# Display.net
KiCad netlist of a schematic drawn in EAGLE
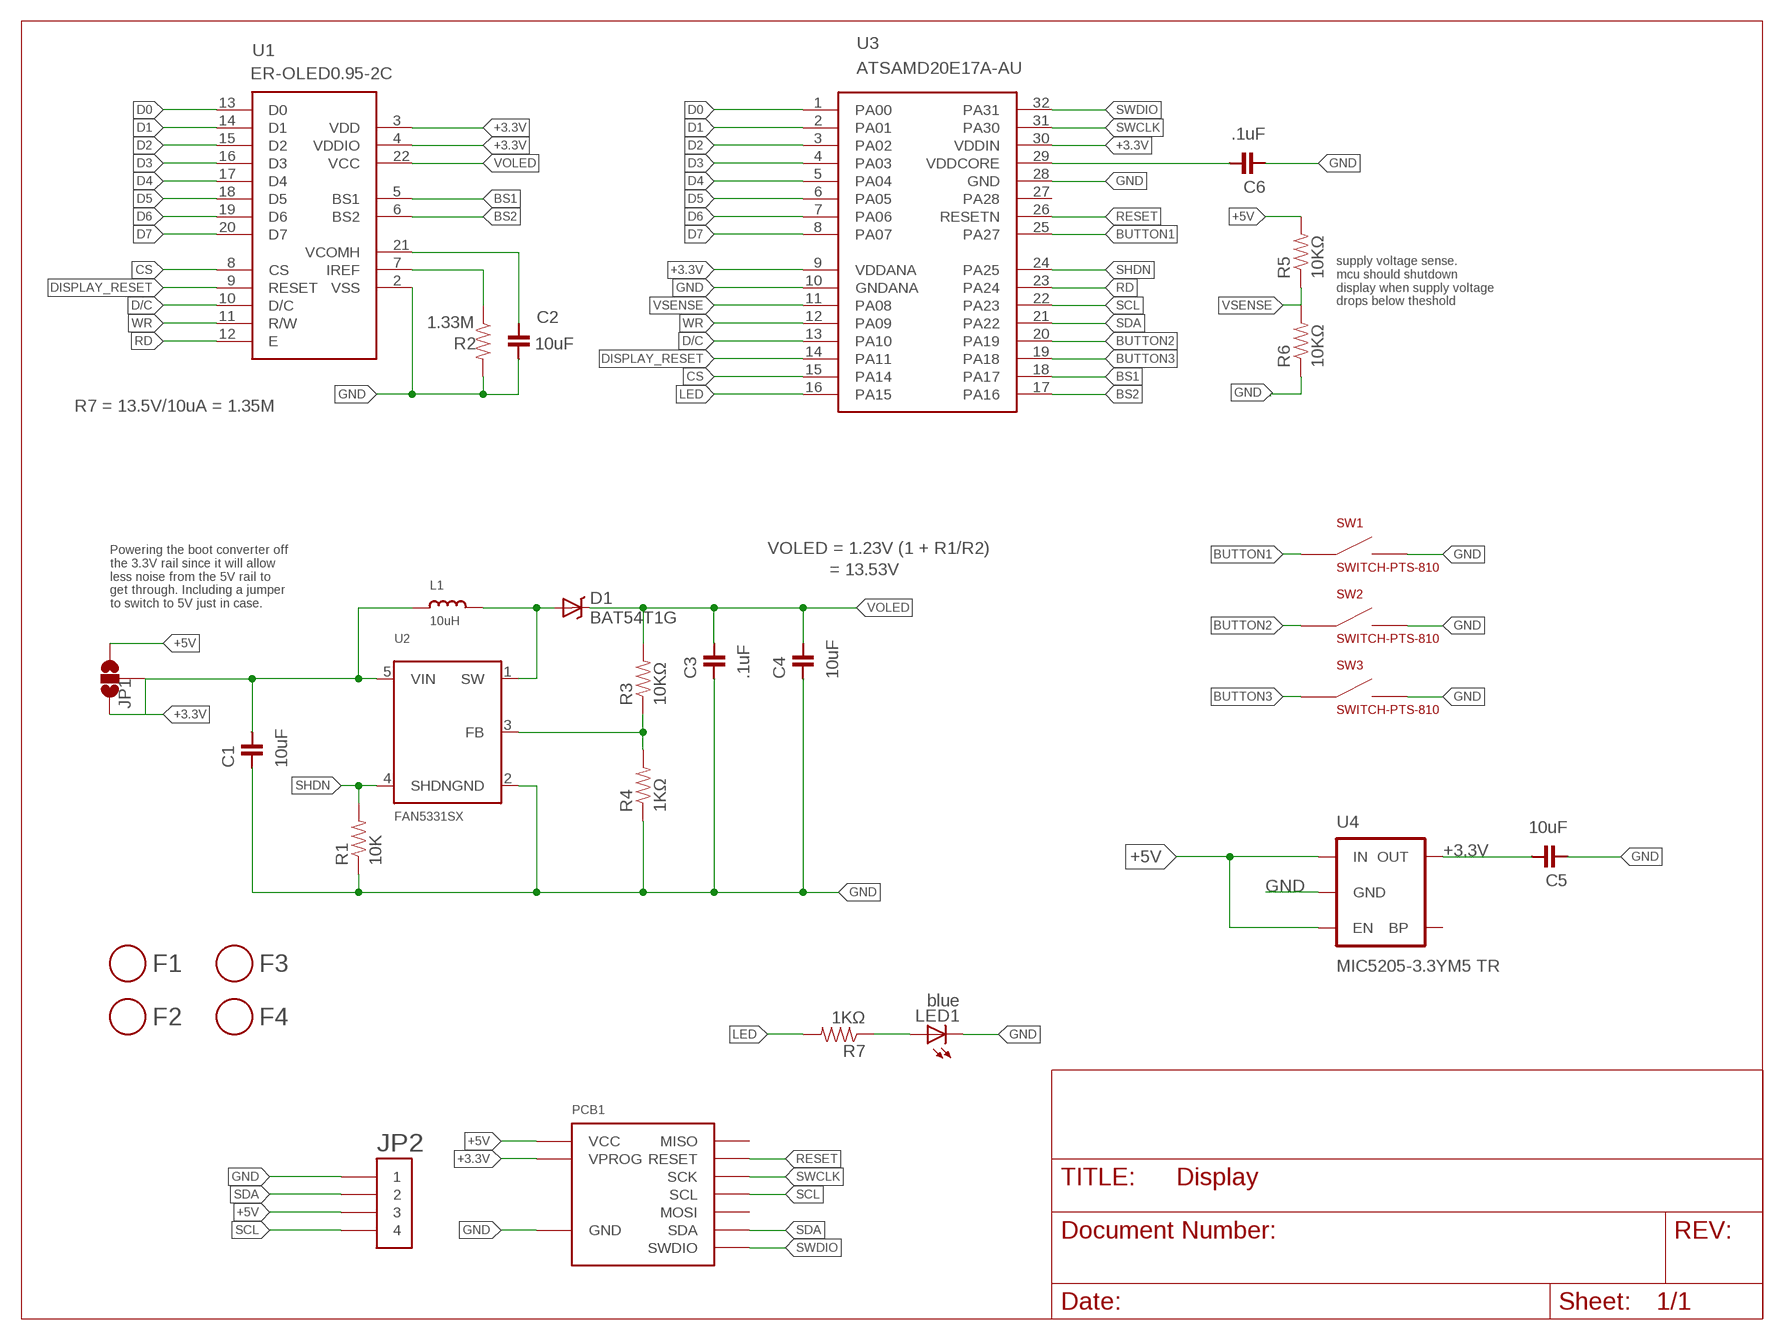
[diagram p0: schematic, sheet 1]

(export (version "E")
  (design (tool "Eeschema 10.0.6"))
  (components
    (comp (ref "C1")
      (value "10uF")
      (footprint "eagle-import:0603")
      (fields (field (name "PARTNUM") "GRM188R61C106MA73D"))
      (libsource (lib "eagle-import") (part "CAPACITOR-10UF"))
    )
    (comp (ref "C2")
      (value "10uF")
      (footprint "eagle-import:0603")
      (fields (field (name "PARTNUM") "GRM188R61C106MA73D"))
      (libsource (lib "eagle-import") (part "CAPACITOR-10UF"))
    )
    (comp (ref "C3")
      (value ".1uF")
      (footprint "eagle-import:0603")
      (fields (field (name "PARTNUM") "C0603C104K5RACTU"))
      (libsource (lib "eagle-import") (part "CAPACITOR-.1UF"))
    )
    (comp (ref "C4")
      (value "10uF")
      (footprint "eagle-import:0603")
      (fields (field (name "PARTNUM") "GRM188R61C106MA73D"))
      (libsource (lib "eagle-import") (part "CAPACITOR-10UF"))
    )
    (comp (ref "C5")
      (value "10uF")
      (footprint "eagle-import:0603")
      (fields (field (name "PARTNUM") "GRM188R61C106MA73D"))
      (libsource (lib "eagle-import") (part "CAPACITOR-10UF"))
    )
    (comp (ref "C6")
      (value ".1uF")
      (footprint "eagle-import:0603")
      (fields (field (name "PARTNUM") "C0603C104K5RACTU"))
      (libsource (lib "eagle-import") (part "CAPACITOR-.1UF"))
    )
    (comp (ref "D1")
      (value "BAT54T1G")
      (footprint "eagle-import:SMP")
      (fields (field (name "PARTNUM") "SS3P3-M3/84A"))
      (libsource (lib "eagle-import") (part "DIODE-SCHOTTKY"))
    )
    (comp (ref "F1")
      (value "FIDUCIAL")
      (footprint "eagle-import:FIDUCIAL_1MM")
      (libsource (lib "eagle-import") (part "FIDUCIAL"))
    )
    (comp (ref "F2")
      (value "FIDUCIAL")
      (footprint "eagle-import:FIDUCIAL_1MM")
      (libsource (lib "eagle-import") (part "FIDUCIAL"))
    )
    (comp (ref "F3")
      (value "FIDUCIAL")
      (footprint "eagle-import:FIDUCIAL_1MM")
      (libsource (lib "eagle-import") (part "FIDUCIAL"))
    )
    (comp (ref "F4")
      (value "FIDUCIAL")
      (footprint "eagle-import:FIDUCIAL_1MM")
      (libsource (lib "eagle-import") (part "FIDUCIAL"))
    )
    (comp (ref "JP1")
      (value "SOLDERJUMPER_2WAYS")
      (footprint "eagle-import:SJ_3")
      (libsource (lib "eagle-import") (part "SOLDERJUMPER_2WAYS"))
    )
    (comp (ref "JP2")
      (value "HEADER-1X4-AMPMODU")
      (footprint "eagle-import:AMPMODU-4P")
      (fields (field (name "PARTNUM") "147721-3"))
      (libsource (lib "eagle-import") (part "HEADER-1X4-AMPMODU"))
    )
    (comp (ref "L1")
      (value "10uH")
      (footprint "eagle-import:INDUCTOR_1007")
      (fields (field (name "PARTNUM") "MPI2520R1-100-R"))
      (libsource (lib "eagle-import") (part "INDUCTOR"))
    )
    (comp (ref "LED1")
      (value "blue")
      (footprint "eagle-import:0805-LED")
      (fields (field (name "PARTNUM") "LTST-C171TBKT"))
      (libsource (lib "eagle-import") (part "LED-0805-BLUE"))
    )
    (comp (ref "PCB1")
      (value "DEVICE-PCB")
      (footprint "eagle-import:DEVICE-PCB")
      (fields
        (field (name "BOARD") "Display")
        (field (name "PARTNUM") "Display PCB")
        (field (name "VERSION") "4")
      )
      (libsource (lib "eagle-import") (part "DEVICE-PCB"))
    )
    (comp (ref "R1")
      (value "10K")
      (footprint "eagle-import:0603")
      (fields (field (name "PARTNUM") "ERJ-3EKF1002V"))
      (libsource (lib "eagle-import") (part "RESISTOR-10KΩ"))
    )
    (comp (ref "R2")
      (value "1.33M")
      (footprint "eagle-import:0603")
      (fields (field (name "PARTNUM") "ERJ-3EKF1304V"))
      (libsource (lib "eagle-import") (part "RESISTOR-0603"))
    )
    (comp (ref "R3")
      (value "10KΩ")
      (footprint "eagle-import:0603")
      (fields (field (name "PARTNUM") "ERJ-3EKF1002V"))
      (libsource (lib "eagle-import") (part "RESISTOR-10KΩ"))
    )
    (comp (ref "R4")
      (value "1KΩ")
      (footprint "eagle-import:0603")
      (fields (field (name "PARTNUM") "ERJ-3EKF1001V"))
      (libsource (lib "eagle-import") (part "RESISTOR-1KΩ"))
    )
    (comp (ref "R5")
      (value "10KΩ")
      (footprint "eagle-import:0603")
      (fields (field (name "PARTNUM") "ERJ-3EKF1002V"))
      (libsource (lib "eagle-import") (part "RESISTOR-10KΩ"))
    )
    (comp (ref "R6")
      (value "10KΩ")
      (footprint "eagle-import:0603")
      (fields (field (name "PARTNUM") "ERJ-3EKF1002V"))
      (libsource (lib "eagle-import") (part "RESISTOR-10KΩ"))
    )
    (comp (ref "R7")
      (value "1KΩ")
      (footprint "eagle-import:0603")
      (fields (field (name "PARTNUM") "ERJ-3EKF1001V"))
      (libsource (lib "eagle-import") (part "RESISTOR-1KΩ"))
    )
    (comp (ref "SW1")
      (value "SWITCH-PTS-810")
      (footprint "eagle-import:TACT-SWITCH-PTS-810")
      (fields (field (name "PARTNUM") "PTS810 SJM 250 SMTR LFS"))
      (libsource (lib "eagle-import") (part "SWITCH-PTS-810"))
    )
    (comp (ref "SW2")
      (value "SWITCH-PTS-810")
      (footprint "eagle-import:TACT-SWITCH-PTS-810")
      (fields (field (name "PARTNUM") "PTS810 SJM 250 SMTR LFS"))
      (libsource (lib "eagle-import") (part "SWITCH-PTS-810"))
    )
    (comp (ref "SW3")
      (value "SWITCH-PTS-810")
      (footprint "eagle-import:TACT-SWITCH-PTS-810")
      (fields (field (name "PARTNUM") "PTS810 SJM 250 SMTR LFS"))
      (libsource (lib "eagle-import") (part "SWITCH-PTS-810"))
    )
    (comp (ref "U1")
      (value "ER-OLED0.95-2C")
      (footprint "eagle-import:FPC-24-REVERSE")
      (fields (field (name "MANUFACTURER") "buydisplay.com"))
      (libsource (lib "eagle-import") (part "OLED-COLORREVERSE"))
    )
    (comp (ref "U2")
      (value "FAN5331SX")
      (footprint "eagle-import:SOT23-5")
      (libsource (lib "eagle-import") (part "FAN5331"))
    )
    (comp (ref "U3")
      (value "ATSAMD20E17A-AU")
      (footprint "eagle-import:TQFP-32")
      (libsource (lib "eagle-import") (part "SAMD21E"))
    )
    (comp (ref "U4")
      (value "MIC5205-3.3YM5 TR")
      (footprint "eagle-import:SOT23-5")
      (libsource (lib "eagle-import") (part "VREG-MIC5205-3.3V"))
    )
  )
  (nets
    (net (code "1") (name "+3.3V") (class "Default")
      (node (ref "C1") (pin "1") (pinfunction "1_1") (pintype "passive"))
      (node (ref "C5") (pin "1") (pinfunction "1_1") (pintype "passive"))
      (node (ref "JP1") (pin "1") (pinfunction "1_1") (pintype "passive"))
      (node (ref "JP1") (pin "2") (pinfunction "2_2") (pintype "passive"))
      (node (ref "L1") (pin "P$1") (pinfunction "1_P$1") (pintype "passive"))
      (node (ref "PCB1") (pin "VPROG") (pinfunction "VPROG_VPROG") (pintype "bidirectional"))
      (node (ref "U1") (pin "3") (pinfunction "VDD_3") (pintype "bidirectional"))
      (node (ref "U1") (pin "4") (pinfunction "VDDIO_4") (pintype "bidirectional"))
      (node (ref "U2") (pin "5") (pinfunction "VIN_5") (pintype "bidirectional"))
      (node (ref "U3") (pin "30") (pinfunction "VDDIN_30") (pintype "bidirectional"))
      (node (ref "U3") (pin "9") (pinfunction "VDDANA_9") (pintype "bidirectional"))
      (node (ref "U4") (pin "5") (pinfunction "OUT_5") (pintype "passive"))
    )
    (net (code "2") (name "+5V") (class "Default")
      (node (ref "JP1") (pin "3") (pinfunction "3_3") (pintype "passive"))
      (node (ref "JP2") (pin "P$5") (pinfunction "3_P$5") (pintype "bidirectional"))
      (node (ref "JP2") (pin "P$6") (pinfunction "3_P$6") (pintype "bidirectional"))
      (node (ref "PCB1") (pin "VCC") (pinfunction "VCC_VCC") (pintype "bidirectional"))
      (node (ref "R5") (pin "2") (pinfunction "2_2") (pintype "passive"))
      (node (ref "U4") (pin "1") (pinfunction "IN_1") (pintype "input"))
      (node (ref "U4") (pin "3") (pinfunction "EN_3") (pintype "input"))
    )
    (net (code "3") (name "BS1") (class "Default")
      (node (ref "U1") (pin "5") (pinfunction "BS1_5") (pintype "bidirectional"))
      (node (ref "U3") (pin "18") (pinfunction "PA17_18") (pintype "bidirectional"))
    )
    (net (code "4") (name "BS2") (class "Default")
      (node (ref "U1") (pin "6") (pinfunction "BS2_6") (pintype "bidirectional"))
      (node (ref "U3") (pin "17") (pinfunction "PA16_17") (pintype "bidirectional"))
    )
    (net (code "5") (name "BUTTON1") (class "Default")
      (node (ref "SW1") (pin "P$1") (pinfunction "POS1_P$1") (pintype "bidirectional"))
      (node (ref "SW1") (pin "P$2") (pinfunction "POS1_P$2") (pintype "bidirectional"))
      (node (ref "U3") (pin "25") (pinfunction "PA27_25") (pintype "bidirectional"))
    )
    (net (code "6") (name "BUTTON2") (class "Default")
      (node (ref "SW2") (pin "P$1") (pinfunction "POS1_P$1") (pintype "bidirectional"))
      (node (ref "SW2") (pin "P$2") (pinfunction "POS1_P$2") (pintype "bidirectional"))
      (node (ref "U3") (pin "20") (pinfunction "PA19_20") (pintype "bidirectional"))
    )
    (net (code "7") (name "BUTTON3") (class "Default")
      (node (ref "SW3") (pin "P$1") (pinfunction "POS1_P$1") (pintype "bidirectional"))
      (node (ref "SW3") (pin "P$2") (pinfunction "POS1_P$2") (pintype "bidirectional"))
      (node (ref "U3") (pin "19") (pinfunction "PA18_19") (pintype "bidirectional"))
    )
    (net (code "8") (name "CS") (class "Default")
      (node (ref "U1") (pin "8") (pinfunction "CS_8") (pintype "bidirectional"))
      (node (ref "U3") (pin "15") (pinfunction "PA14_15") (pintype "bidirectional"))
    )
    (net (code "9") (name "D0") (class "Default")
      (node (ref "U1") (pin "13") (pinfunction "D0_13") (pintype "bidirectional"))
      (node (ref "U3") (pin "1") (pinfunction "PA00_1") (pintype "bidirectional"))
    )
    (net (code "10") (name "D1") (class "Default")
      (node (ref "U1") (pin "14") (pinfunction "D1_14") (pintype "bidirectional"))
      (node (ref "U3") (pin "2") (pinfunction "PA01_2") (pintype "bidirectional"))
    )
    (net (code "11") (name "D2") (class "Default")
      (node (ref "U1") (pin "15") (pinfunction "D2_15") (pintype "bidirectional"))
      (node (ref "U3") (pin "3") (pinfunction "PA02_3") (pintype "bidirectional"))
    )
    (net (code "12") (name "D3") (class "Default")
      (node (ref "U1") (pin "16") (pinfunction "D3_16") (pintype "bidirectional"))
      (node (ref "U3") (pin "4") (pinfunction "PA03_4") (pintype "bidirectional"))
    )
    (net (code "13") (name "D4") (class "Default")
      (node (ref "U1") (pin "17") (pinfunction "D4_17") (pintype "bidirectional"))
      (node (ref "U3") (pin "5") (pinfunction "PA04_5") (pintype "bidirectional"))
    )
    (net (code "14") (name "D5") (class "Default")
      (node (ref "U1") (pin "18") (pinfunction "D5_18") (pintype "bidirectional"))
      (node (ref "U3") (pin "6") (pinfunction "PA05_6") (pintype "bidirectional"))
    )
    (net (code "15") (name "D6") (class "Default")
      (node (ref "U1") (pin "19") (pinfunction "D6_19") (pintype "bidirectional"))
      (node (ref "U3") (pin "7") (pinfunction "PA06_7") (pintype "bidirectional"))
    )
    (net (code "16") (name "D7") (class "Default")
      (node (ref "U1") (pin "20") (pinfunction "D7_20") (pintype "bidirectional"))
      (node (ref "U3") (pin "8") (pinfunction "PA07_8") (pintype "bidirectional"))
    )
    (net (code "17") (name "DISPLAY_RESET") (class "Default")
      (node (ref "U1") (pin "9") (pinfunction "RESET_9") (pintype "bidirectional"))
      (node (ref "U3") (pin "14") (pinfunction "PA11_14") (pintype "bidirectional"))
    )
    (net (code "18") (name "D{slash}C") (class "Default")
      (node (ref "U1") (pin "10") (pinfunction "D/C_10") (pintype "bidirectional"))
      (node (ref "U3") (pin "13") (pinfunction "PA10_13") (pintype "bidirectional"))
    )
    (net (code "19") (name "GND") (class "Default")
      (node (ref "C1") (pin "2") (pinfunction "2_2") (pintype "passive"))
      (node (ref "C2") (pin "2") (pinfunction "2_2") (pintype "passive"))
      (node (ref "C3") (pin "2") (pinfunction "2_2") (pintype "passive"))
      (node (ref "C4") (pin "2") (pinfunction "2_2") (pintype "passive"))
      (node (ref "C5") (pin "2") (pinfunction "2_2") (pintype "passive"))
      (node (ref "C6") (pin "2") (pinfunction "2_2") (pintype "passive"))
      (node (ref "JP2") (pin "P$1") (pinfunction "1_P$1") (pintype "bidirectional"))
      (node (ref "JP2") (pin "P$2") (pinfunction "1_P$2") (pintype "bidirectional"))
      (node (ref "LED1") (pin "C") (pinfunction "C_C") (pintype "passive"))
      (node (ref "PCB1") (pin "GND") (pinfunction "GND_GND") (pintype "bidirectional"))
      (node (ref "R1") (pin "1") (pinfunction "1_1") (pintype "passive"))
      (node (ref "R2") (pin "2") (pinfunction "2_2") (pintype "passive"))
      (node (ref "R4") (pin "1") (pinfunction "1_1") (pintype "passive"))
      (node (ref "R6") (pin "1") (pinfunction "1_1") (pintype "passive"))
      (node (ref "SW1") (pin "P$3") (pinfunction "NEG1_P$3") (pintype "bidirectional"))
      (node (ref "SW1") (pin "P$4") (pinfunction "NEG1_P$4") (pintype "bidirectional"))
      (node (ref "SW2") (pin "P$3") (pinfunction "NEG1_P$3") (pintype "bidirectional"))
      (node (ref "SW2") (pin "P$4") (pinfunction "NEG1_P$4") (pintype "bidirectional"))
      (node (ref "SW3") (pin "P$3") (pinfunction "NEG1_P$3") (pintype "bidirectional"))
      (node (ref "SW3") (pin "P$4") (pinfunction "NEG1_P$4") (pintype "bidirectional"))
      (node (ref "U1") (pin "2") (pinfunction "VSS_2") (pintype "bidirectional"))
      (node (ref "U2") (pin "2") (pinfunction "GND_2") (pintype "bidirectional"))
      (node (ref "U3") (pin "10") (pinfunction "GNDANA_10") (pintype "bidirectional"))
      (node (ref "U3") (pin "28") (pinfunction "GND_28") (pintype "bidirectional"))
      (node (ref "U4") (pin "2") (pinfunction "GND_2") (pintype "input"))
    )
    (net (code "20") (name "LED") (class "Default")
      (node (ref "R7") (pin "2") (pinfunction "2_2") (pintype "passive"))
      (node (ref "U3") (pin "16") (pinfunction "PA15_16") (pintype "bidirectional"))
    )
    (net (code "21") (name "Net-(L1-2)") (class "Default")
      (node (ref "D1") (pin "A") (pinfunction "A_A") (pintype "passive"))
      (node (ref "L1") (pin "P$2") (pinfunction "2_P$2") (pintype "passive"))
      (node (ref "U2") (pin "1") (pinfunction "SW_1") (pintype "bidirectional"))
    )
    (net (code "22") (name "Net-(LED1-PadA)") (class "Default")
      (node (ref "LED1") (pin "A") (pinfunction "A_A") (pintype "passive"))
      (node (ref "R7") (pin "1") (pinfunction "1_1") (pintype "passive"))
    )
    (net (code "23") (name "Net-(U1-IREF)") (class "Default")
      (node (ref "R2") (pin "1") (pinfunction "1_1") (pintype "passive"))
      (node (ref "U1") (pin "7") (pinfunction "IREF_7") (pintype "bidirectional"))
    )
    (net (code "24") (name "Net-(U1-VCOMH)") (class "Default")
      (node (ref "C2") (pin "1") (pinfunction "1_1") (pintype "passive"))
      (node (ref "U1") (pin "21") (pinfunction "VCOMH_21") (pintype "bidirectional"))
    )
    (net (code "25") (name "Net-(U2-FB)") (class "Default")
      (node (ref "R3") (pin "1") (pinfunction "1_1") (pintype "passive"))
      (node (ref "R4") (pin "2") (pinfunction "2_2") (pintype "passive"))
      (node (ref "U2") (pin "3") (pinfunction "FB_3") (pintype "bidirectional"))
    )
    (net (code "26") (name "Net-(U3-VDDCORE)") (class "Default")
      (node (ref "C6") (pin "1") (pinfunction "1_1") (pintype "passive"))
      (node (ref "U3") (pin "29") (pinfunction "VDDCORE_29") (pintype "bidirectional"))
    )
    (net (code "27") (name "RD") (class "Default")
      (node (ref "U1") (pin "12") (pinfunction "E_12") (pintype "bidirectional"))
      (node (ref "U3") (pin "23") (pinfunction "PA24_23") (pintype "bidirectional"))
    )
    (net (code "28") (name "RESET") (class "Default")
      (node (ref "PCB1") (pin "RESET") (pinfunction "RESET_RESET") (pintype "bidirectional"))
      (node (ref "U3") (pin "26") (pinfunction "RESETN_26") (pintype "bidirectional"))
    )
    (net (code "29") (name "SCL") (class "Default")
      (node (ref "JP2") (pin "P$7") (pinfunction "4_P$7") (pintype "bidirectional"))
      (node (ref "JP2") (pin "P$8") (pinfunction "4_P$8") (pintype "bidirectional"))
      (node (ref "PCB1") (pin "SCL") (pinfunction "SCL_SCL") (pintype "bidirectional"))
      (node (ref "U3") (pin "22") (pinfunction "PA23_22") (pintype "bidirectional"))
    )
    (net (code "30") (name "SDA") (class "Default")
      (node (ref "JP2") (pin "P$3") (pinfunction "2_P$3") (pintype "bidirectional"))
      (node (ref "JP2") (pin "P$4") (pinfunction "2_P$4") (pintype "bidirectional"))
      (node (ref "PCB1") (pin "SDA") (pinfunction "SDA_SDA") (pintype "bidirectional"))
      (node (ref "U3") (pin "21") (pinfunction "PA22_21") (pintype "bidirectional"))
    )
    (net (code "31") (name "SHDN") (class "Default")
      (node (ref "R1") (pin "2") (pinfunction "2_2") (pintype "passive"))
      (node (ref "U2") (pin "4") (pinfunction "SHDN_4") (pintype "bidirectional"))
      (node (ref "U3") (pin "24") (pinfunction "PA25_24") (pintype "bidirectional"))
    )
    (net (code "32") (name "SWCLK") (class "Default")
      (node (ref "PCB1") (pin "CLK") (pinfunction "SCK_CLK") (pintype "bidirectional"))
      (node (ref "U3") (pin "31") (pinfunction "PA30_31") (pintype "bidirectional"))
    )
    (net (code "33") (name "SWDIO") (class "Default")
      (node (ref "PCB1") (pin "SWDIO") (pinfunction "SWDIO_SWDIO") (pintype "bidirectional"))
      (node (ref "U3") (pin "32") (pinfunction "PA31_32") (pintype "bidirectional"))
    )
    (net (code "34") (name "VOLED") (class "Default")
      (node (ref "C3") (pin "1") (pinfunction "1_1") (pintype "passive"))
      (node (ref "C4") (pin "1") (pinfunction "1_1") (pintype "passive"))
      (node (ref "D1") (pin "C") (pinfunction "C_C") (pintype "passive"))
      (node (ref "R3") (pin "2") (pinfunction "2_2") (pintype "passive"))
      (node (ref "U1") (pin "22") (pinfunction "VCC_22") (pintype "bidirectional"))
    )
    (net (code "35") (name "VSENSE") (class "Default")
      (node (ref "R5") (pin "1") (pinfunction "1_1") (pintype "passive"))
      (node (ref "R6") (pin "2") (pinfunction "2_2") (pintype "passive"))
      (node (ref "U3") (pin "11") (pinfunction "PA08_11") (pintype "bidirectional"))
    )
    (net (code "36") (name "WR") (class "Default")
      (node (ref "U1") (pin "11") (pinfunction "R/W_11") (pintype "bidirectional"))
      (node (ref "U3") (pin "12") (pinfunction "PA09_12") (pintype "bidirectional"))
    )
    (net (code "37") (name "unconnected-(PCB1-PadMISO)") (class "Default")
      (node (ref "PCB1") (pin "MISO") (pinfunction "MISO_MISO") (pintype "bidirectional"))
    )
    (net (code "38") (name "unconnected-(PCB1-PadMOSI)") (class "Default")
      (node (ref "PCB1") (pin "MOSI") (pinfunction "MOSI_MOSI") (pintype "bidirectional"))
    )
    (net (code "39") (name "unconnected-(U3-PA28-Pad27)") (class "Default")
      (node (ref "U3") (pin "27") (pinfunction "PA28_27") (pintype "bidirectional"))
    )
    (net (code "40") (name "unconnected-(U4-BP-Pad4)") (class "Default")
      (node (ref "U4") (pin "4") (pinfunction "BP_4") (pintype "input"))
    )
  )
)
